# Additional_Feature.net
KiCad netlist of a schematic drawn in Altium Designer
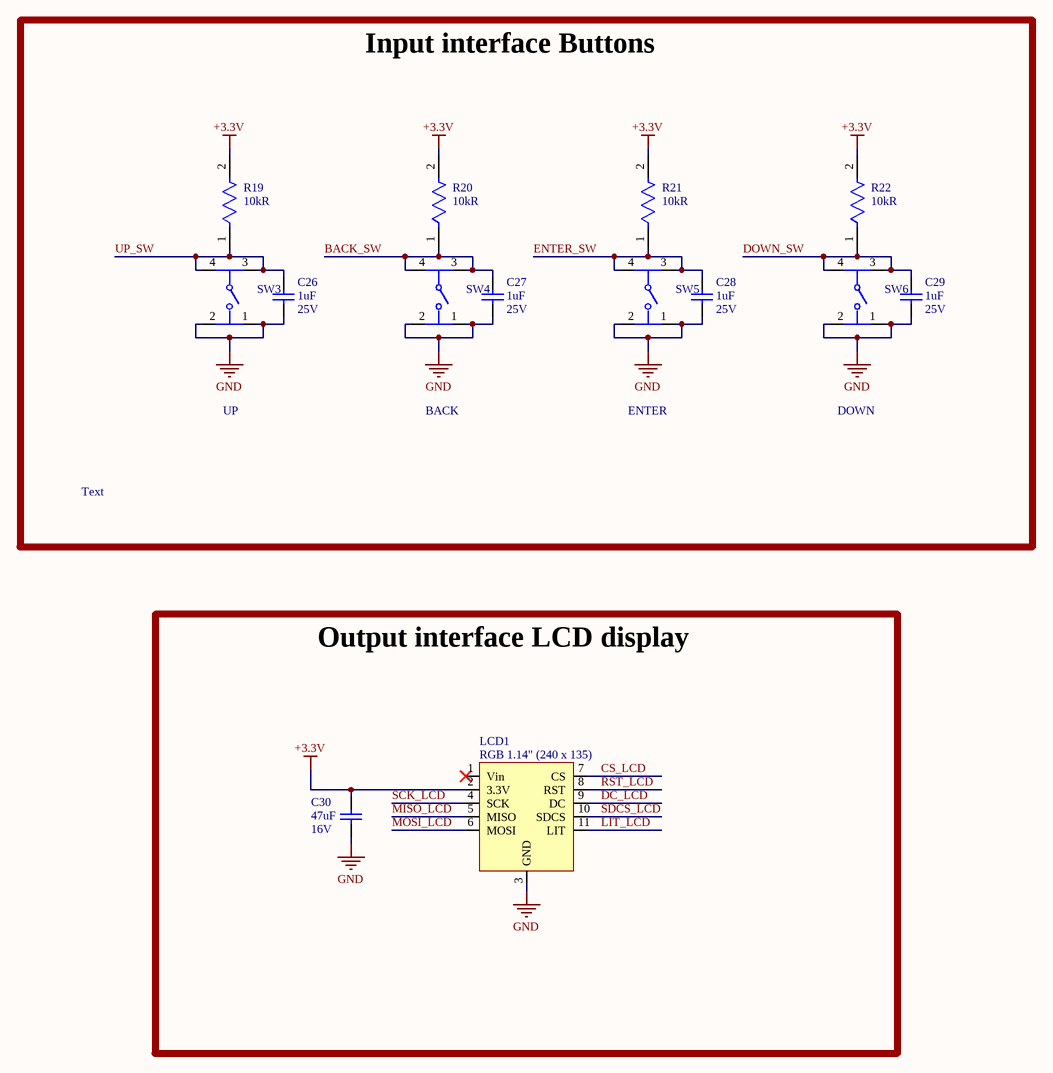
[diagram p0: Additional Feature.SchDoc]

(export (version "E")
  (design (tool "Eeschema 10.0.6"))
  (components
    (comp (ref "C26")
      (value "1uF")
      (footprint "FP-CC0603-DA-IPC_B")
      (fields (field (name "RATED DC VOLTAGE (URDC)") "25V") (field (name "Comment") "1uF 25V 0603"))
      (libsource (lib "2025 Bright Manufacturing Challenge") (part "CAP"))
    )
    (comp (ref "C27")
      (value "1uF")
      (footprint "FP-CC0603-DA-IPC_B")
      (fields (field (name "RATED DC VOLTAGE (URDC)") "25V") (field (name "Comment") "1uF 25V 0603"))
      (libsource (lib "2025 Bright Manufacturing Challenge") (part "CAP"))
    )
    (comp (ref "C28")
      (value "1uF")
      (footprint "FP-CC0603-DA-IPC_B")
      (fields (field (name "RATED DC VOLTAGE (URDC)") "25V") (field (name "Comment") "1uF 25V 0603"))
      (libsource (lib "2025 Bright Manufacturing Challenge") (part "CAP"))
    )
    (comp (ref "C29")
      (value "1uF")
      (footprint "FP-CC0603-DA-IPC_B")
      (fields (field (name "RATED DC VOLTAGE (URDC)") "25V") (field (name "Comment") "1uF 25V 0603"))
      (libsource (lib "2025 Bright Manufacturing Challenge") (part "CAP"))
    )
    (comp (ref "C30")
      (value "47uF")
      (footprint "FP-1210-L_3_2_0_3-W_2_5_0-MFG")
      (fields (field (name "RATED DC VOLTAGE (URDC)") "16V") (field (name "Comment") "CAP"))
      (libsource (lib "2025 Bright Manufacturing Challenge") (part "CAP"))
    )
    (comp (ref "LCD1")
      (value "RGB 1.14\" (240 x 135)")
      (footprint "LCD Display:PCBComponent_1")
      (description "GRAPHIC DISPLAY TFT RGB 1.14\"")
      (fields
        (field (name "MANUFACTURER") "Adafruit Industries LLC")
        (field (name "MANUFACTURER PART NUMBER") "4383")
      )
      (libsource (lib "LCD Display") (part "RGB 1.14{dblquote} (240 x 135)"))
    )
    (comp (ref "R19")
      (value "10kR")
      (footprint "RESC1608X55X25ML10T15")
      (fields
        (field (name "TOLERANCE") "5%")
        (field (name "POWER") "100mW")
        (field (name "Comment") "10KOhm 0603")
      )
      (libsource (lib "2025 Bright Manufacturing Challenge") (part "1029c3af85768c4190bb7ad29bc67b5"))
    )
    (comp (ref "R20")
      (value "10kR")
      (footprint "RESC1608X55X25ML10T15")
      (fields
        (field (name "TOLERANCE") "5%")
        (field (name "POWER") "100mW")
        (field (name "Comment") "10KOhm 0603")
      )
      (libsource (lib "2025 Bright Manufacturing Challenge") (part "1029c3af85768c4190bb7ad29bc67b5"))
    )
    (comp (ref "R21")
      (value "10kR")
      (footprint "RESC1608X55X25ML10T15")
      (fields
        (field (name "TOLERANCE") "5%")
        (field (name "POWER") "100mW")
        (field (name "Comment") "10KOhm 0603")
      )
      (libsource (lib "2025 Bright Manufacturing Challenge") (part "1029c3af85768c4190bb7ad29bc67b5"))
    )
    (comp (ref "R22")
      (value "10kR")
      (footprint "RESC1608X55X25ML10T15")
      (fields
        (field (name "TOLERANCE") "5%")
        (field (name "POWER") "100mW")
        (field (name "Comment") "10KOhm 0603")
      )
      (libsource (lib "2025 Bright Manufacturing Challenge") (part "1029c3af85768c4190bb7ad29bc67b5"))
    )
    (comp (ref "SW3")
      (value "PTS645SM43SMTR92LFS")
      (footprint "FP-PTS645SM43SMTR92LFS-MFG")
      (libsource (lib "2025 Bright Manufacturing Challenge") (part "1adf0dd01260c80cf25a44bfd6b99ba"))
    )
    (comp (ref "SW4")
      (value "PTS645SM43SMTR92LFS")
      (footprint "FP-PTS645SM43SMTR92LFS-MFG")
      (libsource (lib "2025 Bright Manufacturing Challenge") (part "1adf0dd01260c80cf25a44bfd6b99ba"))
    )
    (comp (ref "SW5")
      (value "PTS645SM43SMTR92LFS")
      (footprint "FP-PTS645SM43SMTR92LFS-MFG")
      (libsource (lib "2025 Bright Manufacturing Challenge") (part "1adf0dd01260c80cf25a44bfd6b99ba"))
    )
    (comp (ref "SW6")
      (value "PTS645SM43SMTR92LFS")
      (footprint "FP-PTS645SM43SMTR92LFS-MFG")
      (libsource (lib "2025 Bright Manufacturing Challenge") (part "1adf0dd01260c80cf25a44bfd6b99ba"))
    )
  )
  (nets
    (net (code "1") (name "+3.3V") (class "Default")
      (node (ref "C30") (pin "2") (pinfunction "2_2") (pintype "passive"))
      (node (ref "LCD1") (pin "2") (pinfunction "3.3V_2") (pintype "passive"))
      (node (ref "R19") (pin "2") (pinfunction "2_2") (pintype "passive"))
      (node (ref "R20") (pin "2") (pinfunction "2_2") (pintype "passive"))
      (node (ref "R21") (pin "2") (pinfunction "2_2") (pintype "passive"))
      (node (ref "R22") (pin "2") (pinfunction "2_2") (pintype "passive"))
    )
    (net (code "2") (name "/BACK_SW") (class "Default")
      (node (ref "C27") (pin "2") (pinfunction "2_2") (pintype "passive"))
      (node (ref "R20") (pin "1") (pinfunction "1_1") (pintype "passive"))
      (node (ref "SW4") (pin "3") (pinfunction "3_3") (pintype "passive"))
      (node (ref "SW4") (pin "4") (pinfunction "4_4") (pintype "passive"))
    )
    (net (code "3") (name "/CS_LCD") (class "Default")
      (node (ref "LCD1") (pin "7") (pinfunction "CS_7") (pintype "passive"))
    )
    (net (code "4") (name "/DC_LCD") (class "Default")
      (node (ref "LCD1") (pin "9") (pinfunction "DC_9") (pintype "passive"))
    )
    (net (code "5") (name "/DOWN_SW") (class "Default")
      (node (ref "C29") (pin "2") (pinfunction "2_2") (pintype "passive"))
      (node (ref "R22") (pin "1") (pinfunction "1_1") (pintype "passive"))
      (node (ref "SW6") (pin "3") (pinfunction "3_3") (pintype "passive"))
      (node (ref "SW6") (pin "4") (pinfunction "4_4") (pintype "passive"))
    )
    (net (code "6") (name "/ENTER_SW") (class "Default")
      (node (ref "C28") (pin "2") (pinfunction "2_2") (pintype "passive"))
      (node (ref "R21") (pin "1") (pinfunction "1_1") (pintype "passive"))
      (node (ref "SW5") (pin "3") (pinfunction "3_3") (pintype "passive"))
      (node (ref "SW5") (pin "4") (pinfunction "4_4") (pintype "passive"))
    )
    (net (code "7") (name "/LIT_LCD") (class "Default")
      (node (ref "LCD1") (pin "11") (pinfunction "LIT_11") (pintype "power_in"))
    )
    (net (code "8") (name "/MISO_LCD") (class "Default")
      (node (ref "LCD1") (pin "5") (pinfunction "MISO_5") (pintype "passive"))
    )
    (net (code "9") (name "/MOSI_LCD") (class "Default")
      (node (ref "LCD1") (pin "6") (pinfunction "MOSI_6") (pintype "passive"))
    )
    (net (code "10") (name "/RST_LCD") (class "Default")
      (node (ref "LCD1") (pin "8") (pinfunction "RST_8") (pintype "passive"))
    )
    (net (code "11") (name "/SCK_LCD") (class "Default")
      (node (ref "LCD1") (pin "4") (pinfunction "SCK_4") (pintype "passive"))
    )
    (net (code "12") (name "/SDCS_LCD") (class "Default")
      (node (ref "LCD1") (pin "10") (pinfunction "SDCS_10") (pintype "passive"))
    )
    (net (code "13") (name "/UP_SW") (class "Default")
      (node (ref "C26") (pin "2") (pinfunction "2_2") (pintype "passive"))
      (node (ref "R19") (pin "1") (pinfunction "1_1") (pintype "passive"))
      (node (ref "SW3") (pin "3") (pinfunction "3_3") (pintype "passive"))
      (node (ref "SW3") (pin "4") (pinfunction "4_4") (pintype "passive"))
    )
    (net (code "14") (name "GND") (class "Default")
      (node (ref "C26") (pin "1") (pinfunction "1_1") (pintype "passive"))
      (node (ref "C27") (pin "1") (pinfunction "1_1") (pintype "passive"))
      (node (ref "C28") (pin "1") (pinfunction "1_1") (pintype "passive"))
      (node (ref "C29") (pin "1") (pinfunction "1_1") (pintype "passive"))
      (node (ref "C30") (pin "1") (pinfunction "1_1") (pintype "passive"))
      (node (ref "LCD1") (pin "3") (pinfunction "GND_3") (pintype "power_in"))
      (node (ref "SW3") (pin "1") (pinfunction "1_1") (pintype "passive"))
      (node (ref "SW3") (pin "2") (pinfunction "2_2") (pintype "passive"))
      (node (ref "SW4") (pin "1") (pinfunction "1_1") (pintype "passive"))
      (node (ref "SW4") (pin "2") (pinfunction "2_2") (pintype "passive"))
      (node (ref "SW5") (pin "1") (pinfunction "1_1") (pintype "passive"))
      (node (ref "SW5") (pin "2") (pinfunction "2_2") (pintype "passive"))
      (node (ref "SW6") (pin "1") (pinfunction "1_1") (pintype "passive"))
      (node (ref "SW6") (pin "2") (pinfunction "2_2") (pintype "passive"))
    )
    (net (code "15") (name "unconnected-(LCD1-Vin-Pad1)") (class "Default")
      (node (ref "LCD1") (pin "1") (pinfunction "Vin_1") (pintype "power_in+no_connect"))
    )
  )
)
